# Power.net
KiCad netlist of a schematic drawn in Altium Designer
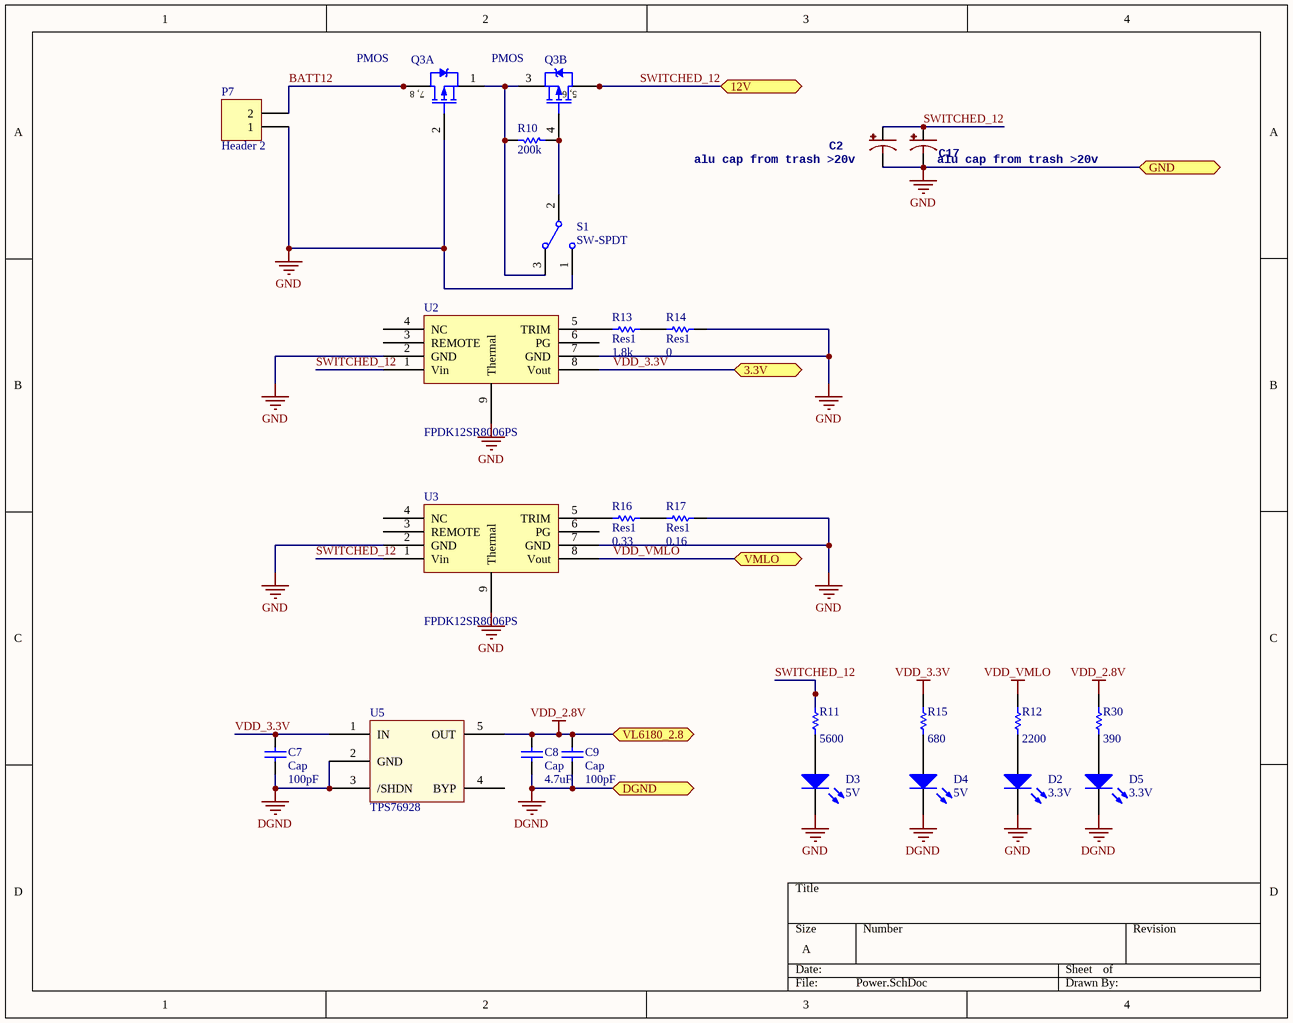
[diagram p0: Power.SchDoc]

(export (version "E")
  (design (tool "Eeschema 10.0.6"))
  (components
    (comp (ref "C2")
      (value "alu cap from trash >20v")
      (footprint "PANASONIC_D")
      (libsource (lib "SparkFun-Passives") (part "CAP_POLD"))
    )
    (comp (ref "C7")
      (value "Cap")
      (footprint "CAP_0805")
      (description "Capacitor")
      (fields (field (name "ALTIUM_VALUE") "100pF") (field (name "PUBLISHER") "Altium Limited"))
      (libsource (lib "Miscellaneous Devices") (part "Cap"))
    )
    (comp (ref "C8")
      (value "Cap")
      (footprint "CAP_0805")
      (description "Capacitor")
      (fields (field (name "ALTIUM_VALUE") "4.7uF") (field (name "PUBLISHER") "Altium Limited"))
      (libsource (lib "Miscellaneous Devices") (part "Cap"))
    )
    (comp (ref "C9")
      (value "Cap")
      (footprint "CAP_0805")
      (description "Capacitor")
      (fields (field (name "ALTIUM_VALUE") "100pF") (field (name "PUBLISHER") "Altium Limited"))
      (libsource (lib "Miscellaneous Devices") (part "Cap"))
    )
    (comp (ref "C17")
      (value "alu cap from trash >20v")
      (footprint "PANASONIC_D")
      (libsource (lib "SparkFun-Passives") (part "CAP_POLD"))
    )
    (comp (ref "D2")
      (value "3.3V")
      (footprint "LED_0805_GREEN")
      (description "LED 1206 green")
      (fields (field (name "PUBLISHER") "Altium Limited"))
      (libsource (lib "Miscellaneous Devices") (part "LED0"))
    )
    (comp (ref "D3")
      (value "5V")
      (footprint "LED_0805_GREEN")
      (description "LED 1206 green")
      (fields (field (name "PUBLISHER") "Altium Limited"))
      (libsource (lib "Miscellaneous Devices") (part "LED0"))
    )
    (comp (ref "D4")
      (value "5V")
      (footprint "LED_0805_GREEN")
      (description "LED 1206 green")
      (fields (field (name "PUBLISHER") "Altium Limited"))
      (libsource (lib "Miscellaneous Devices") (part "LED0"))
    )
    (comp (ref "D5")
      (value "3.3V")
      (footprint "LED_0805_GREEN")
      (description "LED 1206 green")
      (fields (field (name "PUBLISHER") "Altium Limited"))
      (libsource (lib "Miscellaneous Devices") (part "LED0"))
    )
    (comp (ref "P7")
      (value "Header 2")
      (footprint "HX2.54-2")
      (description "Header, 2-Pin")
      (fields (field (name "PUBLISHER") "Altium Limited"))
      (libsource (lib "Miscellaneous Connectors") (part "Header 2"))
    )
    (comp (ref "Q3")
      (value "PMOS")
      (footprint "SOIC_E200_8")
      (description "Dual PMOS")
      (fields (field (name "PUBLISHER") "Altium Limited"))
      (libsource (lib "IR Discrete MOSFET - Power") (part "IRF7316"))
    )
    (comp (ref "R10")
      (value "200k")
      (footprint "RES_0805")
      (description "Resistor")
      (fields (field (name "Comment") "Res") (field (name "PUBLISHER") "Altium Limited"))
      (libsource (lib "Miscellaneous Devices") (part "Res1"))
    )
    (comp (ref "R11")
      (value "5600")
      (footprint "RES_0805")
      (description "Resistor")
      (fields (field (name "Comment") "Res") (field (name "PUBLISHER") "Altium Limited"))
      (libsource (lib "Miscellaneous Devices") (part "Res1"))
    )
    (comp (ref "R12")
      (value "2200")
      (footprint "RES_0805")
      (description "Resistor")
      (fields (field (name "Comment") "Res") (field (name "PUBLISHER") "Altium Limited"))
      (libsource (lib "Miscellaneous Devices") (part "Res1"))
    )
    (comp (ref "R13")
      (value "Res1")
      (footprint "RES_0805")
      (description "Resistor")
      (fields (field (name "ALTIUM_VALUE") "1.8k") (field (name "PUBLISHER") "Altium Limited"))
      (libsource (lib "SmartMouse2016") (part "Res1"))
    )
    (comp (ref "R14")
      (value "Res1")
      (footprint "RES_0805")
      (description "Resistor")
      (fields (field (name "ALTIUM_VALUE") "0") (field (name "PUBLISHER") "Altium Limited"))
      (libsource (lib "SmartMouse2016") (part "Res1"))
    )
    (comp (ref "R15")
      (value "680")
      (footprint "RES_0805")
      (description "Resistor")
      (fields (field (name "Comment") "Res") (field (name "PUBLISHER") "Altium Limited"))
      (libsource (lib "Miscellaneous Devices") (part "Res1"))
    )
    (comp (ref "R16")
      (value "Res1")
      (footprint "RES_0805")
      (description "Resistor")
      (fields (field (name "ALTIUM_VALUE") "0.33") (field (name "PUBLISHER") "Altium Limited"))
      (libsource (lib "SmartMouse2016") (part "Res1"))
    )
    (comp (ref "R17")
      (value "Res1")
      (footprint "RES_0805")
      (description "Resistor")
      (fields (field (name "ALTIUM_VALUE") "0.16") (field (name "PUBLISHER") "Altium Limited"))
      (libsource (lib "SmartMouse2016") (part "Res1"))
    )
    (comp (ref "R30")
      (value "390")
      (footprint "RES_0805")
      (description "Resistor")
      (fields (field (name "Comment") "Res") (field (name "PUBLISHER") "Altium Limited"))
      (libsource (lib "Miscellaneous Devices") (part "Res1"))
    )
    (comp (ref "S1")
      (value "SW-SPDT")
      (footprint "G3T-12AH")
      (description "SPDT Subminiature Toggle Switch, Right Angle Mounting, Vertical Actuation")
      (fields (field (name "PUBLISHER") "Altium Limited"))
      (libsource (lib "Miscellaneous Devices") (part "SW-SPDT"))
    )
    (comp (ref "U2")
      (value "FPDK12SR8006PS")
      (footprint "FPDK12SR8006")
      (libsource (lib "Robotics") (part "FPDK12SR8006PS"))
    )
    (comp (ref "U3")
      (value "FPDK12SR8006PS")
      (footprint "FPDK12SR8006")
      (libsource (lib "Robotics") (part "FPDK12SR8006PS"))
    )
    (comp (ref "U5") (value "TPS76928") (footprint "SOT23-5") (libsource (lib "Robotics") (part "TPS76928")))
  )
  (nets
    (net (code "1") (name "/BATT12") (class "Default")
      (node (ref "P7") (pin "2") (pinfunction "2_2") (pintype "passive"))
      (node (ref "Q3") (pin "7") (pinfunction "D_7") (pintype "passive"))
      (node (ref "Q3") (pin "8") (pinfunction "D_8") (pintype "passive"))
    )
    (net (code "2") (name "/SWITCHED_12") (class "Default")
      (node (ref "C17") (pin "+") (pinfunction "+_+") (pintype "passive"))
      (node (ref "C2") (pin "+") (pinfunction "+_+") (pintype "passive"))
      (node (ref "Q3") (pin "5") (pinfunction "D_5") (pintype "passive"))
      (node (ref "Q3") (pin "6") (pinfunction "D_6") (pintype "passive"))
      (node (ref "R11") (pin "2") (pinfunction "2_2") (pintype "passive"))
      (node (ref "U2") (pin "1") (pinfunction "Vin_1") (pintype "passive"))
      (node (ref "U3") (pin "1") (pinfunction "Vin_1") (pintype "passive"))
    )
    (net (code "3") (name "DGND") (class "Default")
      (node (ref "C7") (pin "1") (pinfunction "1_1") (pintype "passive"))
      (node (ref "C8") (pin "1") (pinfunction "1_1") (pintype "passive"))
      (node (ref "C9") (pin "1") (pinfunction "1_1") (pintype "passive"))
      (node (ref "D4") (pin "2") (pinfunction "K_2") (pintype "passive"))
      (node (ref "D5") (pin "2") (pinfunction "K_2") (pintype "passive"))
      (node (ref "U5") (pin "2") (pinfunction "GND_2") (pintype "passive"))
      (node (ref "U5") (pin "3") (pinfunction "/SHDN_3") (pintype "passive"))
    )
    (net (code "4") (name "GND") (class "Default")
      (node (ref "C17") (pin "-") (pinfunction "-_-") (pintype "passive"))
      (node (ref "C2") (pin "-") (pinfunction "-_-") (pintype "passive"))
      (node (ref "D2") (pin "2") (pinfunction "K_2") (pintype "passive"))
      (node (ref "D3") (pin "2") (pinfunction "K_2") (pintype "passive"))
      (node (ref "P7") (pin "1") (pinfunction "1_1") (pintype "passive"))
      (node (ref "Q3") (pin "2") (pinfunction "G_2") (pintype "passive"))
      (node (ref "R14") (pin "2") (pinfunction "2_2") (pintype "passive"))
      (node (ref "R17") (pin "2") (pinfunction "2_2") (pintype "passive"))
      (node (ref "S1") (pin "1") (pinfunction "1_1") (pintype "passive"))
      (node (ref "U2") (pin "2") (pinfunction "GND_2") (pintype "passive"))
      (node (ref "U2") (pin "7") (pinfunction "GND_7") (pintype "passive"))
      (node (ref "U2") (pin "9") (pinfunction "Thermal_9") (pintype "passive"))
      (node (ref "U3") (pin "2") (pinfunction "GND_2") (pintype "passive"))
      (node (ref "U3") (pin "7") (pinfunction "GND_7") (pintype "passive"))
      (node (ref "U3") (pin "9") (pinfunction "Thermal_9") (pintype "passive"))
    )
    (net (code "5") (name "Net-(D2-A)") (class "Default")
      (node (ref "D2") (pin "1") (pinfunction "A_1") (pintype "passive"))
      (node (ref "R12") (pin "1") (pinfunction "1_1") (pintype "passive"))
    )
    (net (code "6") (name "Net-(D3-A)") (class "Default")
      (node (ref "D3") (pin "1") (pinfunction "A_1") (pintype "passive"))
      (node (ref "R11") (pin "1") (pinfunction "1_1") (pintype "passive"))
    )
    (net (code "7") (name "Net-(D4-A)") (class "Default")
      (node (ref "D4") (pin "1") (pinfunction "A_1") (pintype "passive"))
      (node (ref "R15") (pin "1") (pinfunction "1_1") (pintype "passive"))
    )
    (net (code "8") (name "Net-(D5-A)") (class "Default")
      (node (ref "D5") (pin "1") (pinfunction "A_1") (pintype "passive"))
      (node (ref "R30") (pin "1") (pinfunction "1_1") (pintype "passive"))
    )
    (net (code "9") (name "Net-(Q3A-S)") (class "Default")
      (node (ref "Q3") (pin "1") (pinfunction "S_1") (pintype "passive"))
      (node (ref "Q3") (pin "3") (pinfunction "S_3") (pintype "passive"))
      (node (ref "R10") (pin "1") (pinfunction "1_1") (pintype "passive"))
      (node (ref "S1") (pin "3") (pinfunction "3_3") (pintype "passive"))
    )
    (net (code "10") (name "Net-(Q3B-G)") (class "Default")
      (node (ref "Q3") (pin "4") (pinfunction "G_4") (pintype "passive"))
      (node (ref "R10") (pin "2") (pinfunction "2_2") (pintype "passive"))
      (node (ref "S1") (pin "2") (pinfunction "2_2") (pintype "passive"))
    )
    (net (code "11") (name "Net-(R13-Pad2)") (class "Default")
      (node (ref "R13") (pin "2") (pinfunction "2_2") (pintype "passive"))
      (node (ref "R14") (pin "1") (pinfunction "1_1") (pintype "passive"))
    )
    (net (code "12") (name "Net-(R16-Pad2)") (class "Default")
      (node (ref "R16") (pin "2") (pinfunction "2_2") (pintype "passive"))
      (node (ref "R17") (pin "1") (pinfunction "1_1") (pintype "passive"))
    )
    (net (code "13") (name "Net-(U2-TRIM)") (class "Default")
      (node (ref "R13") (pin "1") (pinfunction "1_1") (pintype "passive"))
      (node (ref "U2") (pin "5") (pinfunction "TRIM_5") (pintype "passive"))
    )
    (net (code "14") (name "Net-(U3-TRIM)") (class "Default")
      (node (ref "R16") (pin "1") (pinfunction "1_1") (pintype "passive"))
      (node (ref "U3") (pin "5") (pinfunction "TRIM_5") (pintype "passive"))
    )
    (net (code "15") (name "VDD_2.8V") (class "Default")
      (node (ref "C8") (pin "2") (pinfunction "2_2") (pintype "passive"))
      (node (ref "C9") (pin "2") (pinfunction "2_2") (pintype "passive"))
      (node (ref "R30") (pin "2") (pinfunction "2_2") (pintype "passive"))
      (node (ref "U5") (pin "5") (pinfunction "OUT_5") (pintype "passive"))
    )
    (net (code "16") (name "VDD_3.3V") (class "Default")
      (node (ref "C7") (pin "2") (pinfunction "2_2") (pintype "passive"))
      (node (ref "R15") (pin "2") (pinfunction "2_2") (pintype "passive"))
      (node (ref "U2") (pin "8") (pinfunction "Vout_8") (pintype "passive"))
      (node (ref "U5") (pin "1") (pinfunction "IN_1") (pintype "passive"))
    )
    (net (code "17") (name "VDD_VMLO") (class "Default")
      (node (ref "R12") (pin "2") (pinfunction "2_2") (pintype "passive"))
      (node (ref "U3") (pin "8") (pinfunction "Vout_8") (pintype "passive"))
    )
    (net (code "18") (name "unconnected-(U2-NC-Pad4)") (class "Default")
      (node (ref "U2") (pin "4") (pinfunction "NC_4") (pintype "passive"))
    )
    (net (code "19") (name "unconnected-(U2-PG-Pad6)") (class "Default")
      (node (ref "U2") (pin "6") (pinfunction "PG_6") (pintype "passive"))
    )
    (net (code "20") (name "unconnected-(U2-REMOTE-Pad3)") (class "Default")
      (node (ref "U2") (pin "3") (pinfunction "REMOTE_3") (pintype "passive"))
    )
    (net (code "21") (name "unconnected-(U3-NC-Pad4)") (class "Default")
      (node (ref "U3") (pin "4") (pinfunction "NC_4") (pintype "passive"))
    )
    (net (code "22") (name "unconnected-(U3-PG-Pad6)") (class "Default")
      (node (ref "U3") (pin "6") (pinfunction "PG_6") (pintype "passive"))
    )
    (net (code "23") (name "unconnected-(U3-REMOTE-Pad3)") (class "Default")
      (node (ref "U3") (pin "3") (pinfunction "REMOTE_3") (pintype "passive"))
    )
    (net (code "24") (name "unconnected-(U5-BYP-Pad4)") (class "Default")
      (node (ref "U5") (pin "4") (pinfunction "BYP_4") (pintype "passive"))
    )
  )
)
